# TUN7_Control.net
KiCad netlist of a schematic drawn in Altium Designer
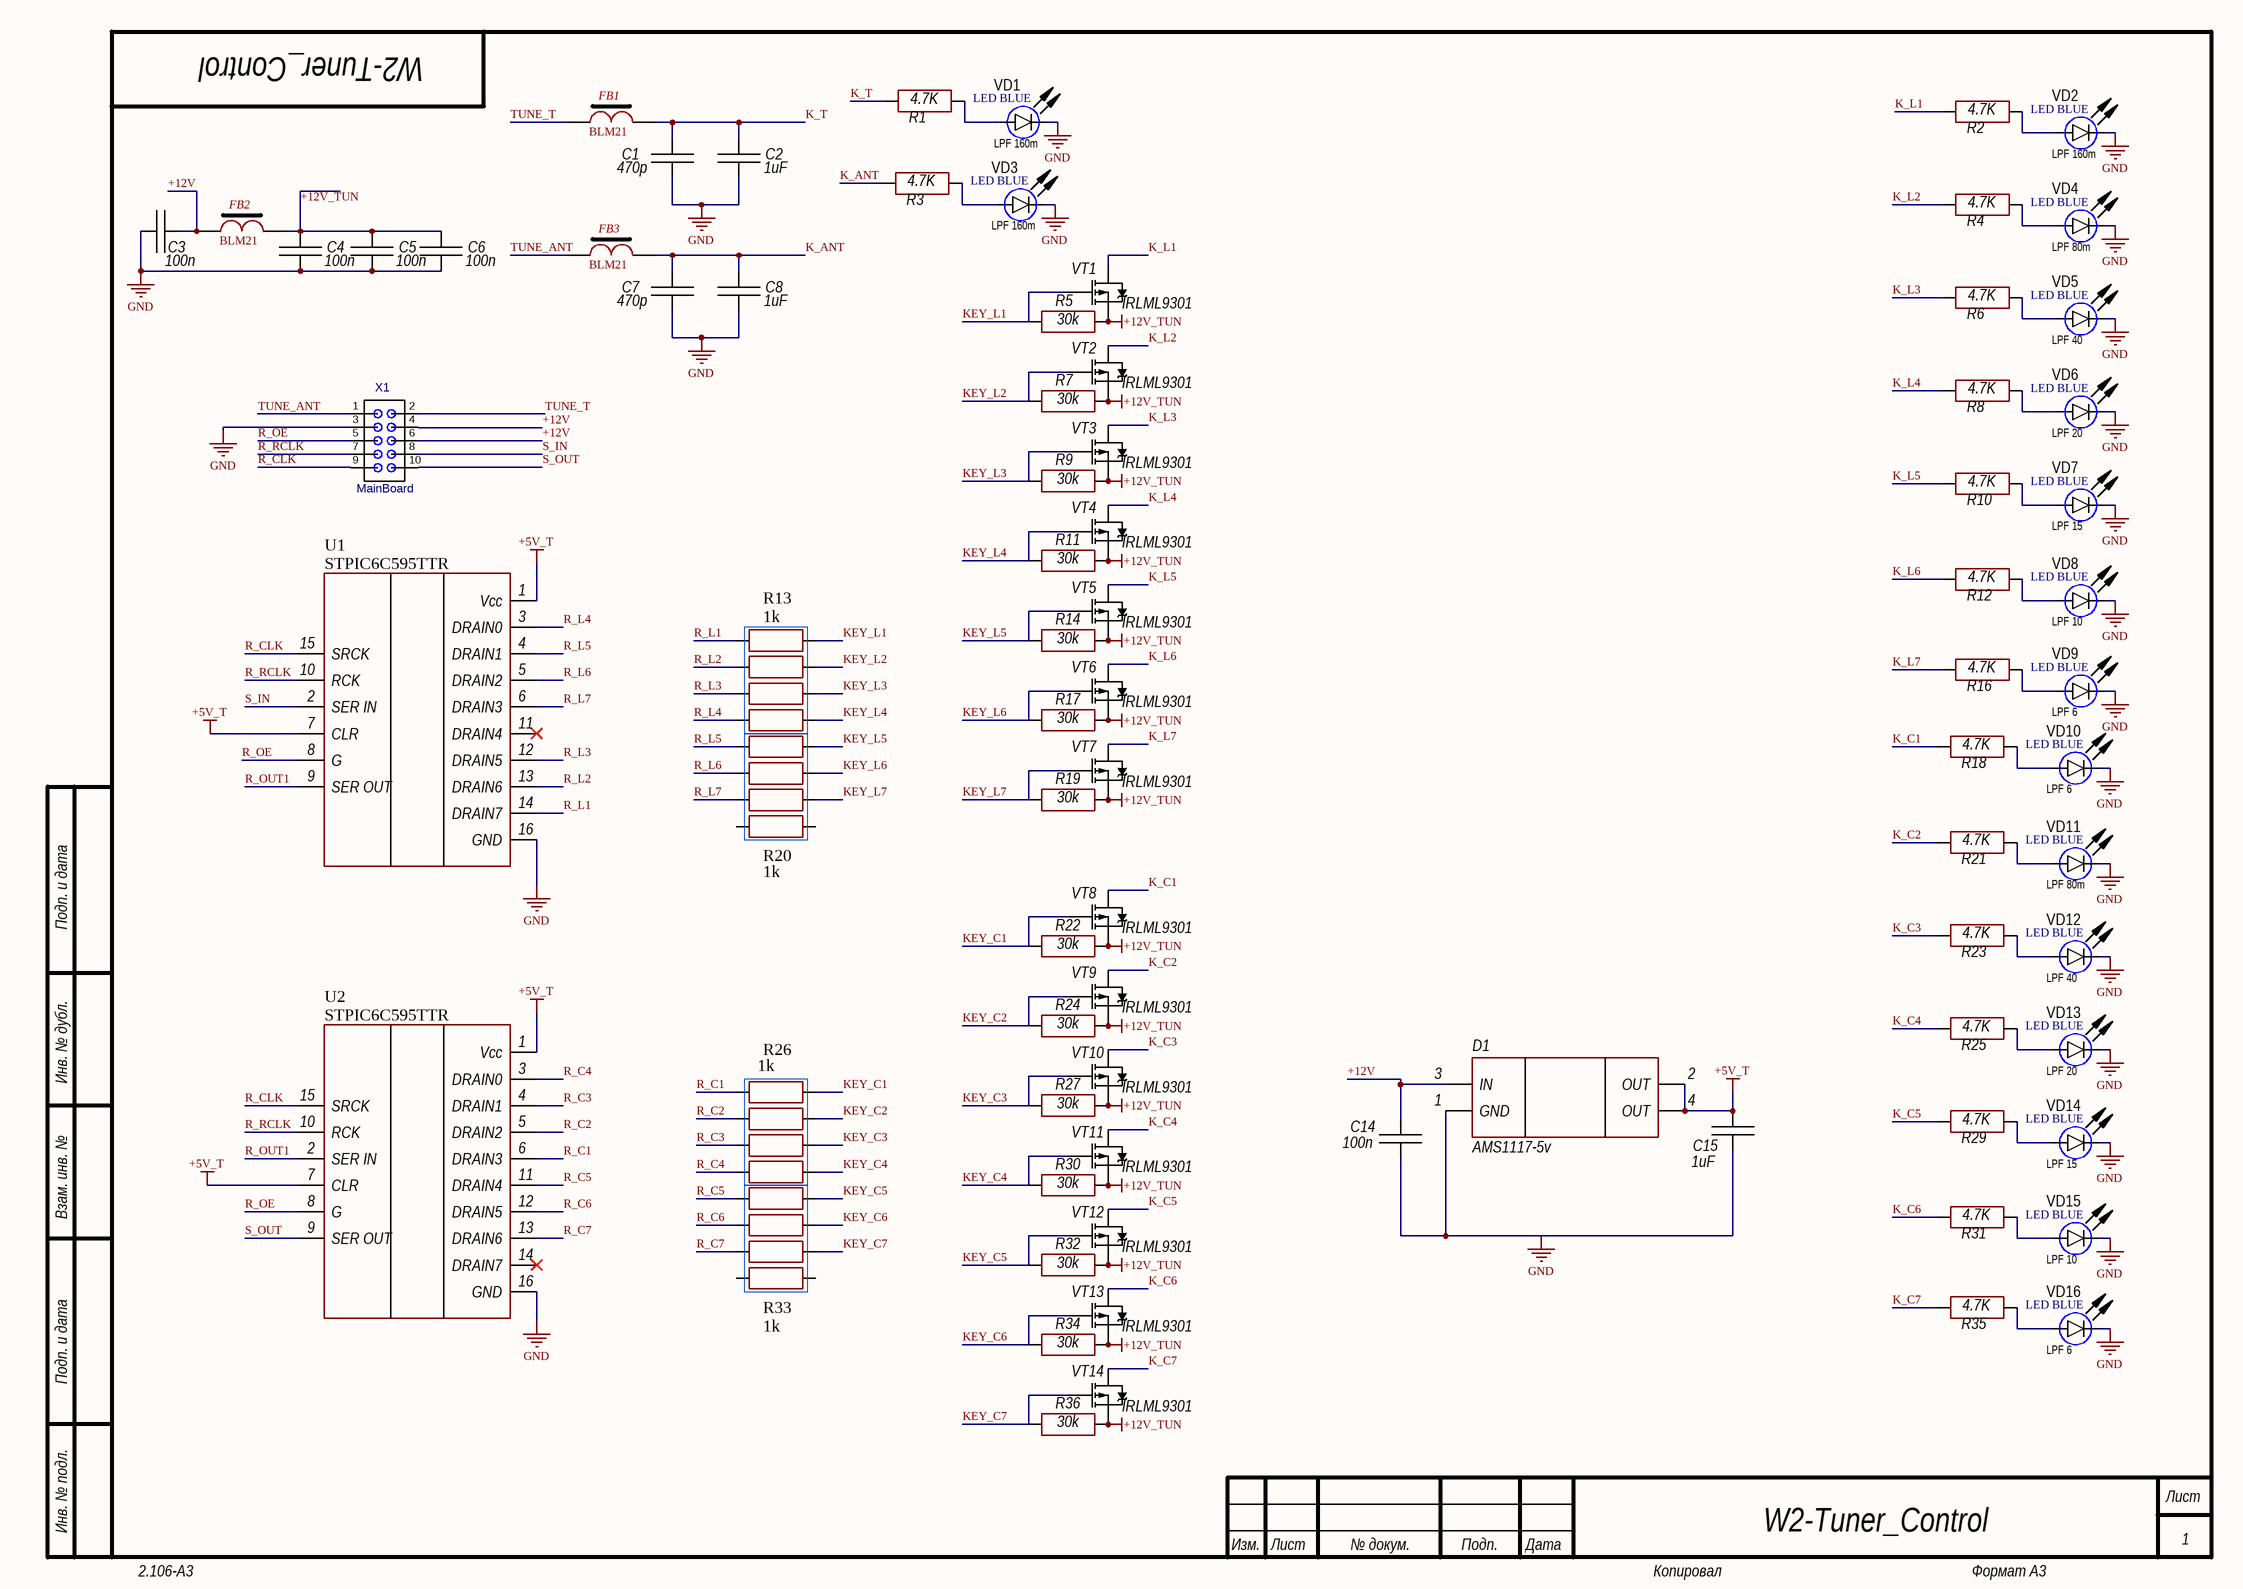
[diagram p0: TUN7_Control.SchDoc]

(export (version "E")
  (design (tool "Eeschema 10.0.6"))
  (components
    (comp (ref "C1")
      (value "470p")
      (footprint "standard:CH0805C")
      (libsource (lib "Discrete") (part "Capacitor"))
    )
    (comp (ref "C2")
      (value "1uF")
      (footprint "standard:CH0805C")
      (libsource (lib "Discrete") (part "Capacitor"))
    )
    (comp (ref "C3")
      (value "100n")
      (footprint "standard:CH0805C")
      (libsource (lib "Discrete") (part "Capacitor"))
    )
    (comp (ref "C4")
      (value "100n")
      (footprint "standard:CH0805C")
      (libsource (lib "Discrete") (part "Capacitor"))
    )
    (comp (ref "C5") (value "100n") (footprint "standard:CH0805C") (libsource (lib "") (part "Capacitor_1")))
    (comp (ref "C6") (value "100n") (footprint "standard:CH0805C") (libsource (lib "") (part "Capacitor_1")))
    (comp (ref "C7")
      (value "470p")
      (footprint "standard:CH0805C")
      (libsource (lib "Discrete") (part "Capacitor"))
    )
    (comp (ref "C8")
      (value "1uF")
      (footprint "standard:CH0805C")
      (libsource (lib "Discrete") (part "Capacitor"))
    )
    (comp (ref "C14")
      (value "100n")
      (footprint "standard:CH0805C")
      (libsource (lib "Discrete") (part "Capacitor"))
    )
    (comp (ref "C15")
      (value "1uF")
      (footprint "standard:CH0805C")
      (libsource (lib "Discrete") (part "Capacitor"))
    )
    (comp (ref "D1")
      (value "AMS1117-5v")
      (footprint "standard:SOT223")
      (description "LDO")
      (fields (field (name "MANUFACTURER") "ON Semiconductor"))
      (libsource (lib "Power Supplies") (part "NCP1117LPST50T3G"))
    )
    (comp (ref "FB1") (value "BLM21") (footprint "CH0805L") (libsource (lib "Discrete") (part "FB-1")))
    (comp (ref "FB2") (value "BLM21") (footprint "CH0805L") (libsource (lib "Discrete") (part "FB-1")))
    (comp (ref "FB3") (value "BLM21") (footprint "CH0805L") (libsource (lib "Discrete") (part "FB-1")))
    (comp (ref "R1")
      (value "4.7K")
      (footprint "standard:CH0805R")
      (libsource (lib "Discrete") (part "Resistor"))
    )
    (comp (ref "R2")
      (value "4.7K")
      (footprint "standard:CH0805R")
      (libsource (lib "Discrete") (part "Resistor"))
    )
    (comp (ref "R3")
      (value "4.7K")
      (footprint "standard:CH0805R")
      (libsource (lib "Discrete") (part "Resistor"))
    )
    (comp (ref "R4")
      (value "4.7K")
      (footprint "standard:CH0805R")
      (libsource (lib "Discrete") (part "Resistor"))
    )
    (comp (ref "R5")
      (value "30k")
      (footprint "standard:CH0805R")
      (libsource (lib "Discrete") (part "Resistor"))
    )
    (comp (ref "R6")
      (value "4.7K")
      (footprint "standard:CH0805R")
      (libsource (lib "Discrete") (part "Resistor"))
    )
    (comp (ref "R7")
      (value "30k")
      (footprint "standard:CH0805R")
      (libsource (lib "Discrete") (part "Resistor"))
    )
    (comp (ref "R8")
      (value "4.7K")
      (footprint "standard:CH0805R")
      (libsource (lib "Discrete") (part "Resistor"))
    )
    (comp (ref "R9")
      (value "30k")
      (footprint "standard:CH0805R")
      (libsource (lib "Discrete") (part "Resistor"))
    )
    (comp (ref "R10")
      (value "4.7K")
      (footprint "standard:CH0805R")
      (libsource (lib "Discrete") (part "Resistor"))
    )
    (comp (ref "R11")
      (value "30k")
      (footprint "standard:CH0805R")
      (libsource (lib "Discrete") (part "Resistor"))
    )
    (comp (ref "R12")
      (value "4.7K")
      (footprint "standard:CH0805R")
      (libsource (lib "Discrete") (part "Resistor"))
    )
    (comp (ref "R13") (value "1k") (footprint "CAT16") (libsource (lib "Discrete") (part "CAT10-0804")))
    (comp (ref "R14")
      (value "30k")
      (footprint "standard:CH0805R")
      (libsource (lib "Discrete") (part "Resistor"))
    )
    (comp (ref "R16")
      (value "4.7K")
      (footprint "standard:CH0805R")
      (libsource (lib "Discrete") (part "Resistor"))
    )
    (comp (ref "R17")
      (value "30k")
      (footprint "standard:CH0805R")
      (libsource (lib "Discrete") (part "Resistor"))
    )
    (comp (ref "R18")
      (value "4.7K")
      (footprint "standard:CH0805R")
      (libsource (lib "Discrete") (part "Resistor"))
    )
    (comp (ref "R19")
      (value "30k")
      (footprint "standard:CH0805R")
      (libsource (lib "Discrete") (part "Resistor"))
    )
    (comp (ref "R20") (value "1k") (footprint "CAT16") (libsource (lib "Discrete") (part "CAT10-0804")))
    (comp (ref "R21")
      (value "4.7K")
      (footprint "standard:CH0805R")
      (libsource (lib "Discrete") (part "Resistor"))
    )
    (comp (ref "R22")
      (value "30k")
      (footprint "standard:CH0805R")
      (libsource (lib "Discrete") (part "Resistor"))
    )
    (comp (ref "R23")
      (value "4.7K")
      (footprint "standard:CH0805R")
      (libsource (lib "Discrete") (part "Resistor"))
    )
    (comp (ref "R24")
      (value "30k")
      (footprint "standard:CH0805R")
      (libsource (lib "Discrete") (part "Resistor"))
    )
    (comp (ref "R25")
      (value "4.7K")
      (footprint "standard:CH0805R")
      (libsource (lib "Discrete") (part "Resistor"))
    )
    (comp (ref "R26") (value "1k") (footprint "CAT16") (libsource (lib "Discrete") (part "CAT10-0804")))
    (comp (ref "R27")
      (value "30k")
      (footprint "standard:CH0805R")
      (libsource (lib "Discrete") (part "Resistor"))
    )
    (comp (ref "R29")
      (value "4.7K")
      (footprint "standard:CH0805R")
      (libsource (lib "Discrete") (part "Resistor"))
    )
    (comp (ref "R30")
      (value "30k")
      (footprint "standard:CH0805R")
      (libsource (lib "Discrete") (part "Resistor"))
    )
    (comp (ref "R31")
      (value "4.7K")
      (footprint "standard:CH0805R")
      (libsource (lib "Discrete") (part "Resistor"))
    )
    (comp (ref "R32")
      (value "30k")
      (footprint "standard:CH0805R")
      (libsource (lib "Discrete") (part "Resistor"))
    )
    (comp (ref "R33") (value "1k") (footprint "CAT16") (libsource (lib "Discrete") (part "CAT10-0804")))
    (comp (ref "R34")
      (value "30k")
      (footprint "standard:CH0805R")
      (libsource (lib "Discrete") (part "Resistor"))
    )
    (comp (ref "R35")
      (value "4.7K")
      (footprint "standard:CH0805R")
      (libsource (lib "Discrete") (part "Resistor"))
    )
    (comp (ref "R36")
      (value "30k")
      (footprint "standard:CH0805R")
      (libsource (lib "Discrete") (part "Resistor"))
    )
    (comp (ref "U1")
      (value "STPIC6C595TTR")
      (footprint "16-TSOP")
      (libsource (lib "Digital") (part "STPIC6C595TTR"))
    )
    (comp (ref "U2")
      (value "STPIC6C595TTR")
      (footprint "16-TSOP")
      (libsource (lib "Digital") (part "STPIC6C595TTR"))
    )
    (comp (ref "VD1")
      (value "LED BLUE")
      (footprint "StandardCase:LED: 0805B")
      (fields
        (field (name "VALUEMANUFACTURERPARTNUMBER") "LED, *, *, *, -55...+150°C")
        (field (name "COLOR") "LPF 160m")
      )
      (libsource (lib "Diode") (part "LED_single"))
    )
    (comp (ref "VD2")
      (value "LED BLUE")
      (footprint "StandardCase:LED: 0805B")
      (fields
        (field (name "VALUEMANUFACTURERPARTNUMBER") "LED, *, *, *, -55...+150°C")
        (field (name "COLOR") "LPF 160m")
      )
      (libsource (lib "Diode") (part "LED_single"))
    )
    (comp (ref "VD3")
      (value "LED BLUE")
      (footprint "StandardCase:LED: 0805B")
      (fields
        (field (name "VALUEMANUFACTURERPARTNUMBER") "LED, *, *, *, -55...+150°C")
        (field (name "COLOR") "LPF 160m")
      )
      (libsource (lib "Diode") (part "LED_single"))
    )
    (comp (ref "VD4")
      (value "LED BLUE")
      (footprint "StandardCase:LED: 0805B")
      (fields
        (field (name "VALUEMANUFACTURERPARTNUMBER") "LED, *, *, *, -55...+150°C")
        (field (name "COLOR") "LPF 80m")
      )
      (libsource (lib "Diode") (part "LED_single"))
    )
    (comp (ref "VD5")
      (value "LED BLUE")
      (footprint "StandardCase:LED: 0805B")
      (fields
        (field (name "VALUEMANUFACTURERPARTNUMBER") "LED, *, *, *, -55...+150°C")
        (field (name "COLOR") "LPF 40")
      )
      (libsource (lib "Diode") (part "LED_single"))
    )
    (comp (ref "VD6")
      (value "LED BLUE")
      (footprint "StandardCase:LED: 0805B")
      (fields
        (field (name "VALUEMANUFACTURERPARTNUMBER") "LED, *, *, *, -55...+150°C")
        (field (name "COLOR") "LPF 20")
      )
      (libsource (lib "Diode") (part "LED_single"))
    )
    (comp (ref "VD7")
      (value "LED BLUE")
      (footprint "StandardCase:LED: 0805B")
      (fields
        (field (name "VALUEMANUFACTURERPARTNUMBER") "LED, *, *, *, -55...+150°C")
        (field (name "COLOR") "LPF 15")
      )
      (libsource (lib "Diode") (part "LED_single"))
    )
    (comp (ref "VD8")
      (value "LED BLUE")
      (footprint "StandardCase:LED: 0805B")
      (fields
        (field (name "VALUEMANUFACTURERPARTNUMBER") "LED, *, *, *, -55...+150°C")
        (field (name "COLOR") "LPF 10")
      )
      (libsource (lib "Diode") (part "LED_single"))
    )
    (comp (ref "VD9")
      (value "LED BLUE")
      (footprint "StandardCase:LED: 0805B")
      (fields
        (field (name "VALUEMANUFACTURERPARTNUMBER") "LED, *, *, *, -55...+150°C")
        (field (name "COLOR") "LPF 6")
      )
      (libsource (lib "Diode") (part "LED_single"))
    )
    (comp (ref "VD10")
      (value "LED BLUE")
      (footprint "StandardCase:LED: 0805B")
      (fields
        (field (name "VALUEMANUFACTURERPARTNUMBER") "LED, *, *, *, -55...+150°C")
        (field (name "COLOR") "LPF 6")
      )
      (libsource (lib "Diode") (part "LED_single"))
    )
    (comp (ref "VD11")
      (value "LED BLUE")
      (footprint "StandardCase:LED: 0805B")
      (fields
        (field (name "VALUEMANUFACTURERPARTNUMBER") "LED, *, *, *, -55...+150°C")
        (field (name "COLOR") "LPF 80m")
      )
      (libsource (lib "Diode") (part "LED_single"))
    )
    (comp (ref "VD12")
      (value "LED BLUE")
      (footprint "StandardCase:LED: 0805B")
      (fields
        (field (name "VALUEMANUFACTURERPARTNUMBER") "LED, *, *, *, -55...+150°C")
        (field (name "COLOR") "LPF 40")
      )
      (libsource (lib "Diode") (part "LED_single"))
    )
    (comp (ref "VD13")
      (value "LED BLUE")
      (footprint "StandardCase:LED: 0805B")
      (fields
        (field (name "VALUEMANUFACTURERPARTNUMBER") "LED, *, *, *, -55...+150°C")
        (field (name "COLOR") "LPF 20")
      )
      (libsource (lib "Diode") (part "LED_single"))
    )
    (comp (ref "VD14")
      (value "LED BLUE")
      (footprint "StandardCase:LED: 0805B")
      (fields
        (field (name "VALUEMANUFACTURERPARTNUMBER") "LED, *, *, *, -55...+150°C")
        (field (name "COLOR") "LPF 15")
      )
      (libsource (lib "Diode") (part "LED_single"))
    )
    (comp (ref "VD15")
      (value "LED BLUE")
      (footprint "StandardCase:LED: 0805B")
      (fields
        (field (name "VALUEMANUFACTURERPARTNUMBER") "LED, *, *, *, -55...+150°C")
        (field (name "COLOR") "LPF 10")
      )
      (libsource (lib "Diode") (part "LED_single"))
    )
    (comp (ref "VD16")
      (value "LED BLUE")
      (footprint "StandardCase:LED: 0805B")
      (fields
        (field (name "VALUEMANUFACTURERPARTNUMBER") "LED, *, *, *, -55...+150°C")
        (field (name "COLOR") "LPF 6")
      )
      (libsource (lib "Diode") (part "LED_single"))
    )
    (comp (ref "VT1")
      (value "IRLML9301")
      (footprint "standard:SOT23_132")
      (description "Mosfet")
      (libsource (lib "Transistor") (part "IRLML9301"))
    )
    (comp (ref "VT2")
      (value "IRLML9301")
      (footprint "standard:SOT23_132")
      (description "Mosfet")
      (libsource (lib "Transistor") (part "IRLML9301"))
    )
    (comp (ref "VT3")
      (value "IRLML9301")
      (footprint "standard:SOT23_132")
      (description "Mosfet")
      (libsource (lib "Transistor") (part "IRLML9301"))
    )
    (comp (ref "VT4")
      (value "IRLML9301")
      (footprint "standard:SOT23_132")
      (description "Mosfet")
      (libsource (lib "Transistor") (part "IRLML9301"))
    )
    (comp (ref "VT5")
      (value "IRLML9301")
      (footprint "standard:SOT23_132")
      (description "Mosfet")
      (libsource (lib "Transistor") (part "IRLML9301"))
    )
    (comp (ref "VT6")
      (value "IRLML9301")
      (footprint "standard:SOT23_132")
      (description "Mosfet")
      (libsource (lib "Transistor") (part "IRLML9301"))
    )
    (comp (ref "VT7")
      (value "IRLML9301")
      (footprint "standard:SOT23_132")
      (description "Mosfet")
      (libsource (lib "Transistor") (part "IRLML9301"))
    )
    (comp (ref "VT8")
      (value "IRLML9301")
      (footprint "standard:SOT23_132")
      (description "Mosfet")
      (libsource (lib "Transistor") (part "IRLML9301"))
    )
    (comp (ref "VT9")
      (value "IRLML9301")
      (footprint "standard:SOT23_132")
      (description "Mosfet")
      (libsource (lib "Transistor") (part "IRLML9301"))
    )
    (comp (ref "VT10")
      (value "IRLML9301")
      (footprint "standard:SOT23_132")
      (description "Mosfet")
      (libsource (lib "Transistor") (part "IRLML9301"))
    )
    (comp (ref "VT11")
      (value "IRLML9301")
      (footprint "standard:SOT23_132")
      (description "Mosfet")
      (libsource (lib "Transistor") (part "IRLML9301"))
    )
    (comp (ref "VT12")
      (value "IRLML9301")
      (footprint "standard:SOT23_132")
      (description "Mosfet")
      (libsource (lib "Transistor") (part "IRLML9301"))
    )
    (comp (ref "VT13")
      (value "IRLML9301")
      (footprint "standard:SOT23_132")
      (description "Mosfet")
      (libsource (lib "Transistor") (part "IRLML9301"))
    )
    (comp (ref "VT14")
      (value "IRLML9301")
      (footprint "standard:SOT23_132")
      (description "Mosfet")
      (libsource (lib "Transistor") (part "IRLML9301"))
    )
    (comp (ref "X1")
      (value "MainBoard")
      (footprint "CON: BH-10")
      (description "2*5 Pin")
      (libsource (lib "*") (part "IDC10"))
    )
  )
  (nets
    (net (code "1") (name "+5V_T") (class "Default")
      (node (ref "C15") (pin "2") (pinfunction "2_2") (pintype "power_in"))
      (node (ref "D1") (pin "2") (pinfunction "OUT_2") (pintype "passive"))
      (node (ref "D1") (pin "4") (pinfunction "OUT_4") (pintype "passive"))
      (node (ref "U1") (pin "1") (pinfunction "Vcc_1") (pintype "passive"))
      (node (ref "U1") (pin "7") (pinfunction "CLR_7") (pintype "passive"))
      (node (ref "U2") (pin "1") (pinfunction "Vcc_1") (pintype "passive"))
      (node (ref "U2") (pin "7") (pinfunction "CLR_7") (pintype "passive"))
    )
    (net (code "2") (name "+12V_TUN") (class "Default")
      (node (ref "C4") (pin "2") (pinfunction "2_2") (pintype "power_in"))
      (node (ref "C5") (pin "2") (pinfunction "2_2") (pintype "power_in"))
      (node (ref "C6") (pin "2") (pinfunction "2_2") (pintype "power_in"))
      (node (ref "FB2") (pin "1") (pinfunction "1_1") (pintype "passive"))
      (node (ref "R11") (pin "1") (pinfunction "1_1") (pintype "passive"))
      (node (ref "R14") (pin "1") (pinfunction "1_1") (pintype "passive"))
      (node (ref "R17") (pin "1") (pinfunction "1_1") (pintype "passive"))
      (node (ref "R19") (pin "1") (pinfunction "1_1") (pintype "passive"))
      (node (ref "R22") (pin "1") (pinfunction "1_1") (pintype "passive"))
      (node (ref "R24") (pin "1") (pinfunction "1_1") (pintype "passive"))
      (node (ref "R27") (pin "1") (pinfunction "1_1") (pintype "passive"))
      (node (ref "R30") (pin "1") (pinfunction "1_1") (pintype "passive"))
      (node (ref "R32") (pin "1") (pinfunction "1_1") (pintype "passive"))
      (node (ref "R34") (pin "1") (pinfunction "1_1") (pintype "passive"))
      (node (ref "R36") (pin "1") (pinfunction "1_1") (pintype "passive"))
      (node (ref "R5") (pin "1") (pinfunction "1_1") (pintype "passive"))
      (node (ref "R7") (pin "1") (pinfunction "1_1") (pintype "passive"))
      (node (ref "R9") (pin "1") (pinfunction "1_1") (pintype "passive"))
      (node (ref "VT1") (pin "2") (pinfunction "S_2") (pintype "passive"))
      (node (ref "VT10") (pin "2") (pinfunction "S_2") (pintype "passive"))
      (node (ref "VT11") (pin "2") (pinfunction "S_2") (pintype "passive"))
      (node (ref "VT12") (pin "2") (pinfunction "S_2") (pintype "passive"))
      (node (ref "VT13") (pin "2") (pinfunction "S_2") (pintype "passive"))
      (node (ref "VT14") (pin "2") (pinfunction "S_2") (pintype "passive"))
      (node (ref "VT2") (pin "2") (pinfunction "S_2") (pintype "passive"))
      (node (ref "VT3") (pin "2") (pinfunction "S_2") (pintype "passive"))
      (node (ref "VT4") (pin "2") (pinfunction "S_2") (pintype "passive"))
      (node (ref "VT5") (pin "2") (pinfunction "S_2") (pintype "passive"))
      (node (ref "VT6") (pin "2") (pinfunction "S_2") (pintype "passive"))
      (node (ref "VT7") (pin "2") (pinfunction "S_2") (pintype "passive"))
      (node (ref "VT8") (pin "2") (pinfunction "S_2") (pintype "passive"))
      (node (ref "VT9") (pin "2") (pinfunction "S_2") (pintype "passive"))
    )
    (net (code "3") (name "/+12V") (class "Default")
      (node (ref "C14") (pin "2") (pinfunction "2_2") (pintype "power_in"))
      (node (ref "C3") (pin "2") (pinfunction "2_2") (pintype "power_in"))
      (node (ref "D1") (pin "3") (pinfunction "IN_3") (pintype "power_in"))
      (node (ref "FB2") (pin "2") (pinfunction "2_2") (pintype "passive"))
      (node (ref "X1") (pin "4") (pinfunction "4_4") (pintype "passive"))
      (node (ref "X1") (pin "6") (pinfunction "6_6") (pintype "passive"))
    )
    (net (code "4") (name "/KEY_C1") (class "Default")
      (node (ref "R22") (pin "2") (pinfunction "2_2") (pintype "passive"))
      (node (ref "R26") (pin "5") (pinfunction "5_5") (pintype "passive"))
      (node (ref "VT8") (pin "1") (pinfunction "G_1") (pintype "passive"))
    )
    (net (code "5") (name "/KEY_C2") (class "Default")
      (node (ref "R24") (pin "2") (pinfunction "2_2") (pintype "passive"))
      (node (ref "R26") (pin "6") (pinfunction "6_6") (pintype "passive"))
      (node (ref "VT9") (pin "1") (pinfunction "G_1") (pintype "passive"))
    )
    (net (code "6") (name "/KEY_C3") (class "Default")
      (node (ref "R26") (pin "7") (pinfunction "7_7") (pintype "passive"))
      (node (ref "R27") (pin "2") (pinfunction "2_2") (pintype "passive"))
      (node (ref "VT10") (pin "1") (pinfunction "G_1") (pintype "passive"))
    )
    (net (code "7") (name "/KEY_C4") (class "Default")
      (node (ref "R26") (pin "8") (pinfunction "8_8") (pintype "passive"))
      (node (ref "R30") (pin "2") (pinfunction "2_2") (pintype "passive"))
      (node (ref "VT11") (pin "1") (pinfunction "G_1") (pintype "passive"))
    )
    (net (code "8") (name "/KEY_C5") (class "Default")
      (node (ref "R32") (pin "2") (pinfunction "2_2") (pintype "passive"))
      (node (ref "R33") (pin "5") (pinfunction "5_5") (pintype "passive"))
      (node (ref "VT12") (pin "1") (pinfunction "G_1") (pintype "passive"))
    )
    (net (code "9") (name "/KEY_C6") (class "Default")
      (node (ref "R33") (pin "6") (pinfunction "6_6") (pintype "passive"))
      (node (ref "R34") (pin "2") (pinfunction "2_2") (pintype "passive"))
      (node (ref "VT13") (pin "1") (pinfunction "G_1") (pintype "passive"))
    )
    (net (code "10") (name "/KEY_C7") (class "Default")
      (node (ref "R33") (pin "7") (pinfunction "7_7") (pintype "passive"))
      (node (ref "R36") (pin "2") (pinfunction "2_2") (pintype "passive"))
      (node (ref "VT14") (pin "1") (pinfunction "G_1") (pintype "passive"))
    )
    (net (code "11") (name "/KEY_L1") (class "Default")
      (node (ref "R13") (pin "5") (pinfunction "5_5") (pintype "passive"))
      (node (ref "R5") (pin "2") (pinfunction "2_2") (pintype "passive"))
      (node (ref "VT1") (pin "1") (pinfunction "G_1") (pintype "passive"))
    )
    (net (code "12") (name "/KEY_L2") (class "Default")
      (node (ref "R13") (pin "6") (pinfunction "6_6") (pintype "passive"))
      (node (ref "R7") (pin "2") (pinfunction "2_2") (pintype "passive"))
      (node (ref "VT2") (pin "1") (pinfunction "G_1") (pintype "passive"))
    )
    (net (code "13") (name "/KEY_L3") (class "Default")
      (node (ref "R13") (pin "7") (pinfunction "7_7") (pintype "passive"))
      (node (ref "R9") (pin "2") (pinfunction "2_2") (pintype "passive"))
      (node (ref "VT3") (pin "1") (pinfunction "G_1") (pintype "passive"))
    )
    (net (code "14") (name "/KEY_L4") (class "Default")
      (node (ref "R11") (pin "2") (pinfunction "2_2") (pintype "passive"))
      (node (ref "R13") (pin "8") (pinfunction "8_8") (pintype "passive"))
      (node (ref "VT4") (pin "1") (pinfunction "G_1") (pintype "passive"))
    )
    (net (code "15") (name "/KEY_L5") (class "Default")
      (node (ref "R14") (pin "2") (pinfunction "2_2") (pintype "passive"))
      (node (ref "R20") (pin "5") (pinfunction "5_5") (pintype "passive"))
      (node (ref "VT5") (pin "1") (pinfunction "G_1") (pintype "passive"))
    )
    (net (code "16") (name "/KEY_L6") (class "Default")
      (node (ref "R17") (pin "2") (pinfunction "2_2") (pintype "passive"))
      (node (ref "R20") (pin "6") (pinfunction "6_6") (pintype "passive"))
      (node (ref "VT6") (pin "1") (pinfunction "G_1") (pintype "passive"))
    )
    (net (code "17") (name "/KEY_L7") (class "Default")
      (node (ref "R19") (pin "2") (pinfunction "2_2") (pintype "passive"))
      (node (ref "R20") (pin "7") (pinfunction "7_7") (pintype "passive"))
      (node (ref "VT7") (pin "1") (pinfunction "G_1") (pintype "passive"))
    )
    (net (code "18") (name "/K_ANT") (class "Default")
      (node (ref "C7") (pin "1") (pinfunction "1_1") (pintype "power_in"))
      (node (ref "C8") (pin "1") (pinfunction "1_1") (pintype "power_in"))
      (node (ref "FB3") (pin "1") (pinfunction "1_1") (pintype "passive"))
      (node (ref "R3") (pin "2") (pinfunction "2_2") (pintype "passive"))
    )
    (net (code "19") (name "/K_C1") (class "Default")
      (node (ref "R18") (pin "2") (pinfunction "2_2") (pintype "passive"))
      (node (ref "VT8") (pin "3") (pinfunction "D_3") (pintype "passive"))
    )
    (net (code "20") (name "/K_C2") (class "Default")
      (node (ref "R21") (pin "2") (pinfunction "2_2") (pintype "passive"))
      (node (ref "VT9") (pin "3") (pinfunction "D_3") (pintype "passive"))
    )
    (net (code "21") (name "/K_C3") (class "Default")
      (node (ref "R23") (pin "2") (pinfunction "2_2") (pintype "passive"))
      (node (ref "VT10") (pin "3") (pinfunction "D_3") (pintype "passive"))
    )
    (net (code "22") (name "/K_C4") (class "Default")
      (node (ref "R25") (pin "2") (pinfunction "2_2") (pintype "passive"))
      (node (ref "VT11") (pin "3") (pinfunction "D_3") (pintype "passive"))
    )
    (net (code "23") (name "/K_C5") (class "Default")
      (node (ref "R29") (pin "2") (pinfunction "2_2") (pintype "passive"))
      (node (ref "VT12") (pin "3") (pinfunction "D_3") (pintype "passive"))
    )
    (net (code "24") (name "/K_C6") (class "Default")
      (node (ref "R31") (pin "2") (pinfunction "2_2") (pintype "passive"))
      (node (ref "VT13") (pin "3") (pinfunction "D_3") (pintype "passive"))
    )
    (net (code "25") (name "/K_C7") (class "Default")
      (node (ref "R35") (pin "2") (pinfunction "2_2") (pintype "passive"))
      (node (ref "VT14") (pin "3") (pinfunction "D_3") (pintype "passive"))
    )
    (net (code "26") (name "/K_L1") (class "Default")
      (node (ref "R2") (pin "2") (pinfunction "2_2") (pintype "passive"))
      (node (ref "VT1") (pin "3") (pinfunction "D_3") (pintype "passive"))
    )
    (net (code "27") (name "/K_L2") (class "Default")
      (node (ref "R4") (pin "2") (pinfunction "2_2") (pintype "passive"))
      (node (ref "VT2") (pin "3") (pinfunction "D_3") (pintype "passive"))
    )
    (net (code "28") (name "/K_L3") (class "Default")
      (node (ref "R6") (pin "2") (pinfunction "2_2") (pintype "passive"))
      (node (ref "VT3") (pin "3") (pinfunction "D_3") (pintype "passive"))
    )
    (net (code "29") (name "/K_L4") (class "Default")
      (node (ref "R8") (pin "2") (pinfunction "2_2") (pintype "passive"))
      (node (ref "VT4") (pin "3") (pinfunction "D_3") (pintype "passive"))
    )
    (net (code "30") (name "/K_L5") (class "Default")
      (node (ref "R10") (pin "2") (pinfunction "2_2") (pintype "passive"))
      (node (ref "VT5") (pin "3") (pinfunction "D_3") (pintype "passive"))
    )
    (net (code "31") (name "/K_L6") (class "Default")
      (node (ref "R12") (pin "2") (pinfunction "2_2") (pintype "passive"))
      (node (ref "VT6") (pin "3") (pinfunction "D_3") (pintype "passive"))
    )
    (net (code "32") (name "/K_L7") (class "Default")
      (node (ref "R16") (pin "2") (pinfunction "2_2") (pintype "passive"))
      (node (ref "VT7") (pin "3") (pinfunction "D_3") (pintype "passive"))
    )
    (net (code "33") (name "/K_T") (class "Default")
      (node (ref "C1") (pin "1") (pinfunction "1_1") (pintype "power_in"))
      (node (ref "C2") (pin "1") (pinfunction "1_1") (pintype "power_in"))
      (node (ref "FB1") (pin "1") (pinfunction "1_1") (pintype "passive"))
      (node (ref "R1") (pin "2") (pinfunction "2_2") (pintype "passive"))
    )
    (net (code "34") (name "/R_C1") (class "Default")
      (node (ref "R26") (pin "1") (pinfunction "1_1") (pintype "passive"))
      (node (ref "U2") (pin "6") (pinfunction "DRAIN3_6") (pintype "passive"))
    )
    (net (code "35") (name "/R_C2") (class "Default")
      (node (ref "R26") (pin "2") (pinfunction "2_2") (pintype "passive"))
      (node (ref "U2") (pin "5") (pinfunction "DRAIN2_5") (pintype "passive"))
    )
    (net (code "36") (name "/R_C3") (class "Default")
      (node (ref "R26") (pin "3") (pinfunction "3_3") (pintype "passive"))
      (node (ref "U2") (pin "4") (pinfunction "DRAIN1_4") (pintype "passive"))
    )
    (net (code "37") (name "/R_C4") (class "Default")
      (node (ref "R26") (pin "4") (pinfunction "4_4") (pintype "passive"))
      (node (ref "U2") (pin "3") (pinfunction "DRAIN0_3") (pintype "passive"))
    )
    (net (code "38") (name "/R_C5") (class "Default")
      (node (ref "R33") (pin "1") (pinfunction "1_1") (pintype "passive"))
      (node (ref "U2") (pin "11") (pinfunction "DRAIN4_11") (pintype "passive"))
    )
    (net (code "39") (name "/R_C6") (class "Default")
      (node (ref "R33") (pin "2") (pinfunction "2_2") (pintype "passive"))
      (node (ref "U2") (pin "12") (pinfunction "DRAIN5_12") (pintype "passive"))
    )
    (net (code "40") (name "/R_C7") (class "Default")
      (node (ref "R33") (pin "3") (pinfunction "3_3") (pintype "passive"))
      (node (ref "U2") (pin "13") (pinfunction "DRAIN6_13") (pintype "passive"))
    )
    (net (code "41") (name "/R_CLK") (class "Default")
      (node (ref "U1") (pin "15") (pinfunction "SRCK_15") (pintype "passive"))
      (node (ref "U2") (pin "15") (pinfunction "SRCK_15") (pintype "passive"))
      (node (ref "X1") (pin "9") (pinfunction "9_9") (pintype "passive"))
    )
    (net (code "42") (name "/R_L1") (class "Default")
      (node (ref "R13") (pin "1") (pinfunction "1_1") (pintype "passive"))
      (node (ref "U1") (pin "14") (pinfunction "DRAIN7_14") (pintype "passive"))
    )
    (net (code "43") (name "/R_L2") (class "Default")
      (node (ref "R13") (pin "2") (pinfunction "2_2") (pintype "passive"))
      (node (ref "U1") (pin "13") (pinfunction "DRAIN6_13") (pintype "passive"))
    )
    (net (code "44") (name "/R_L3") (class "Default")
      (node (ref "R13") (pin "3") (pinfunction "3_3") (pintype "passive"))
      (node (ref "U1") (pin "12") (pinfunction "DRAIN5_12") (pintype "passive"))
    )
    (net (code "45") (name "/R_L4") (class "Default")
      (node (ref "R13") (pin "4") (pinfunction "4_4") (pintype "passive"))
      (node (ref "U1") (pin "3") (pinfunction "DRAIN0_3") (pintype "passive"))
    )
    (net (code "46") (name "/R_L5") (class "Default")
      (node (ref "R20") (pin "1") (pinfunction "1_1") (pintype "passive"))
      (node (ref "U1") (pin "4") (pinfunction "DRAIN1_4") (pintype "passive"))
    )
    (net (code "47") (name "/R_L6") (class "Default")
      (node (ref "R20") (pin "2") (pinfunction "2_2") (pintype "passive"))
      (node (ref "U1") (pin "5") (pinfunction "DRAIN2_5") (pintype "passive"))
    )
    (net (code "48") (name "/R_L7") (class "Default")
      (node (ref "R20") (pin "3") (pinfunction "3_3") (pintype "passive"))
      (node (ref "U1") (pin "6") (pinfunction "DRAIN3_6") (pintype "passive"))
    )
    (net (code "49") (name "/R_OE") (class "Default")
      (node (ref "U1") (pin "8") (pinfunction "G_8") (pintype "passive"))
      (node (ref "U2") (pin "8") (pinfunction "G_8") (pintype "passive"))
      (node (ref "X1") (pin "5") (pinfunction "5_5") (pintype "passive"))
    )
    (net (code "50") (name "/R_OUT1") (class "Default")
      (node (ref "U1") (pin "9") (pinfunction "SER_OUT_9") (pintype "passive"))
      (node (ref "U2") (pin "2") (pinfunction "SER_IN_2") (pintype "passive"))
    )
    (net (code "51") (name "/R_RCLK") (class "Default")
      (node (ref "U1") (pin "10") (pinfunction "RCK_10") (pintype "passive"))
      (node (ref "U2") (pin "10") (pinfunction "RCK_10") (pintype "passive"))
      (node (ref "X1") (pin "7") (pinfunction "7_7") (pintype "passive"))
    )
    (net (code "52") (name "/S_IN") (class "Default")
      (node (ref "U1") (pin "2") (pinfunction "SER_IN_2") (pintype "passive"))
      (node (ref "X1") (pin "8") (pinfunction "8_8") (pintype "passive"))
    )
    (net (code "53") (name "/S_OUT") (class "Default")
      (node (ref "U2") (pin "9") (pinfunction "SER_OUT_9") (pintype "passive"))
      (node (ref "X1") (pin "10") (pinfunction "10_10") (pintype "passive"))
    )
    (net (code "54") (name "/TUNE_ANT") (class "Default")
      (node (ref "FB3") (pin "2") (pinfunction "2_2") (pintype "passive"))
      (node (ref "X1") (pin "1") (pinfunction "1_1") (pintype "passive"))
    )
    (net (code "55") (name "/TUNE_T") (class "Default")
      (node (ref "FB1") (pin "2") (pinfunction "2_2") (pintype "passive"))
      (node (ref "X1") (pin "2") (pinfunction "2_2") (pintype "passive"))
    )
    (net (code "56") (name "GND") (class "Default")
      (node (ref "C1") (pin "2") (pinfunction "2_2") (pintype "power_in"))
      (node (ref "C14") (pin "1") (pinfunction "1_1") (pintype "power_in"))
      (node (ref "C15") (pin "1") (pinfunction "1_1") (pintype "power_in"))
      (node (ref "C2") (pin "2") (pinfunction "2_2") (pintype "power_in"))
      (node (ref "C3") (pin "1") (pinfunction "1_1") (pintype "power_in"))
      (node (ref "C4") (pin "1") (pinfunction "1_1") (pintype "power_in"))
      (node (ref "C5") (pin "1") (pinfunction "1_1") (pintype "power_in"))
      (node (ref "C6") (pin "1") (pinfunction "1_1") (pintype "power_in"))
      (node (ref "C7") (pin "2") (pinfunction "2_2") (pintype "power_in"))
      (node (ref "C8") (pin "2") (pinfunction "2_2") (pintype "power_in"))
      (node (ref "D1") (pin "1") (pinfunction "GND_1") (pintype "passive"))
      (node (ref "U1") (pin "16") (pinfunction "GND_16") (pintype "passive"))
      (node (ref "U2") (pin "16") (pinfunction "GND_16") (pintype "passive"))
      (node (ref "VD1") (pin "2") (pinfunction "C_2") (pintype "passive"))
      (node (ref "VD10") (pin "2") (pinfunction "C_2") (pintype "passive"))
      (node (ref "VD11") (pin "2") (pinfunction "C_2") (pintype "passive"))
      (node (ref "VD12") (pin "2") (pinfunction "C_2") (pintype "passive"))
      (node (ref "VD13") (pin "2") (pinfunction "C_2") (pintype "passive"))
      (node (ref "VD14") (pin "2") (pinfunction "C_2") (pintype "passive"))
      (node (ref "VD15") (pin "2") (pinfunction "C_2") (pintype "passive"))
      (node (ref "VD16") (pin "2") (pinfunction "C_2") (pintype "passive"))
      (node (ref "VD2") (pin "2") (pinfunction "C_2") (pintype "passive"))
      (node (ref "VD3") (pin "2") (pinfunction "C_2") (pintype "passive"))
      (node (ref "VD4") (pin "2") (pinfunction "C_2") (pintype "passive"))
      (node (ref "VD5") (pin "2") (pinfunction "C_2") (pintype "passive"))
      (node (ref "VD6") (pin "2") (pinfunction "C_2") (pintype "passive"))
      (node (ref "VD7") (pin "2") (pinfunction "C_2") (pintype "passive"))
      (node (ref "VD8") (pin "2") (pinfunction "C_2") (pintype "passive"))
      (node (ref "VD9") (pin "2") (pinfunction "C_2") (pintype "passive"))
      (node (ref "X1") (pin "3") (pinfunction "3_3") (pintype "passive"))
    )
    (net (code "57") (name "Net-(VD1-A)") (class "Default")
      (node (ref "R1") (pin "1") (pinfunction "1_1") (pintype "passive"))
      (node (ref "VD1") (pin "1") (pinfunction "A_1") (pintype "passive"))
    )
    (net (code "58") (name "Net-(VD2-A)") (class "Default")
      (node (ref "R2") (pin "1") (pinfunction "1_1") (pintype "passive"))
      (node (ref "VD2") (pin "1") (pinfunction "A_1") (pintype "passive"))
    )
    (net (code "59") (name "Net-(VD3-A)") (class "Default")
      (node (ref "R3") (pin "1") (pinfunction "1_1") (pintype "passive"))
      (node (ref "VD3") (pin "1") (pinfunction "A_1") (pintype "passive"))
    )
    (net (code "60") (name "Net-(VD4-A)") (class "Default")
      (node (ref "R4") (pin "1") (pinfunction "1_1") (pintype "passive"))
      (node (ref "VD4") (pin "1") (pinfunction "A_1") (pintype "passive"))
    )
    (net (code "61") (name "Net-(VD5-A)") (class "Default")
      (node (ref "R6") (pin "1") (pinfunction "1_1") (pintype "passive"))
      (node (ref "VD5") (pin "1") (pinfunction "A_1") (pintype "passive"))
    )
    (net (code "62") (name "Net-(VD6-A)") (class "Default")
      (node (ref "R8") (pin "1") (pinfunction "1_1") (pintype "passive"))
      (node (ref "VD6") (pin "1") (pinfunction "A_1") (pintype "passive"))
    )
    (net (code "63") (name "Net-(VD7-A)") (class "Default")
      (node (ref "R10") (pin "1") (pinfunction "1_1") (pintype "passive"))
      (node (ref "VD7") (pin "1") (pinfunction "A_1") (pintype "passive"))
    )
    (net (code "64") (name "Net-(VD8-A)") (class "Default")
      (node (ref "R12") (pin "1") (pinfunction "1_1") (pintype "passive"))
      (node (ref "VD8") (pin "1") (pinfunction "A_1") (pintype "passive"))
    )
    (net (code "65") (name "Net-(VD9-A)") (class "Default")
      (node (ref "R16") (pin "1") (pinfunction "1_1") (pintype "passive"))
      (node (ref "VD9") (pin "1") (pinfunction "A_1") (pintype "passive"))
    )
    (net (code "66") (name "Net-(VD10-A)") (class "Default")
      (node (ref "R18") (pin "1") (pinfunction "1_1") (pintype "passive"))
      (node (ref "VD10") (pin "1") (pinfunction "A_1") (pintype "passive"))
    )
    (net (code "67") (name "Net-(VD11-A)") (class "Default")
      (node (ref "R21") (pin "1") (pinfunction "1_1") (pintype "passive"))
      (node (ref "VD11") (pin "1") (pinfunction "A_1") (pintype "passive"))
    )
    (net (code "68") (name "Net-(VD12-A)") (class "Default")
      (node (ref "R23") (pin "1") (pinfunction "1_1") (pintype "passive"))
      (node (ref "VD12") (pin "1") (pinfunction "A_1") (pintype "passive"))
    )
    (net (code "69") (name "Net-(VD13-A)") (class "Default")
      (node (ref "R25") (pin "1") (pinfunction "1_1") (pintype "passive"))
      (node (ref "VD13") (pin "1") (pinfunction "A_1") (pintype "passive"))
    )
    (net (code "70") (name "Net-(VD14-A)") (class "Default")
      (node (ref "R29") (pin "1") (pinfunction "1_1") (pintype "passive"))
      (node (ref "VD14") (pin "1") (pinfunction "A_1") (pintype "passive"))
    )
    (net (code "71") (name "Net-(VD15-A)") (class "Default")
      (node (ref "R31") (pin "1") (pinfunction "1_1") (pintype "passive"))
      (node (ref "VD15") (pin "1") (pinfunction "A_1") (pintype "passive"))
    )
    (net (code "72") (name "Net-(VD16-A)") (class "Default")
      (node (ref "R35") (pin "1") (pinfunction "1_1") (pintype "passive"))
      (node (ref "VD16") (pin "1") (pinfunction "A_1") (pintype "passive"))
    )
    (net (code "73") (name "unconnected-(R20-Pad4)") (class "Default")
      (node (ref "R20") (pin "4") (pinfunction "4_4") (pintype "passive"))
    )
    (net (code "74") (name "unconnected-(R20-Pad8)") (class "Default")
      (node (ref "R20") (pin "8") (pinfunction "8_8") (pintype "passive"))
    )
    (net (code "75") (name "unconnected-(R33-Pad4)") (class "Default")
      (node (ref "R33") (pin "4") (pinfunction "4_4") (pintype "passive"))
    )
    (net (code "76") (name "unconnected-(R33-Pad8)") (class "Default")
      (node (ref "R33") (pin "8") (pinfunction "8_8") (pintype "passive"))
    )
    (net (code "77") (name "unconnected-(U1-DRAIN4-Pad11)") (class "Default")
      (node (ref "U1") (pin "11") (pinfunction "DRAIN4_11") (pintype "passive+no_connect"))
    )
    (net (code "78") (name "unconnected-(U2-DRAIN7-Pad14)") (class "Default")
      (node (ref "U2") (pin "14") (pinfunction "DRAIN7_14") (pintype "passive+no_connect"))
    )
  )
)
